# KUBODriver_MCU.net
KiCad netlist of a schematic drawn in Altium Designer
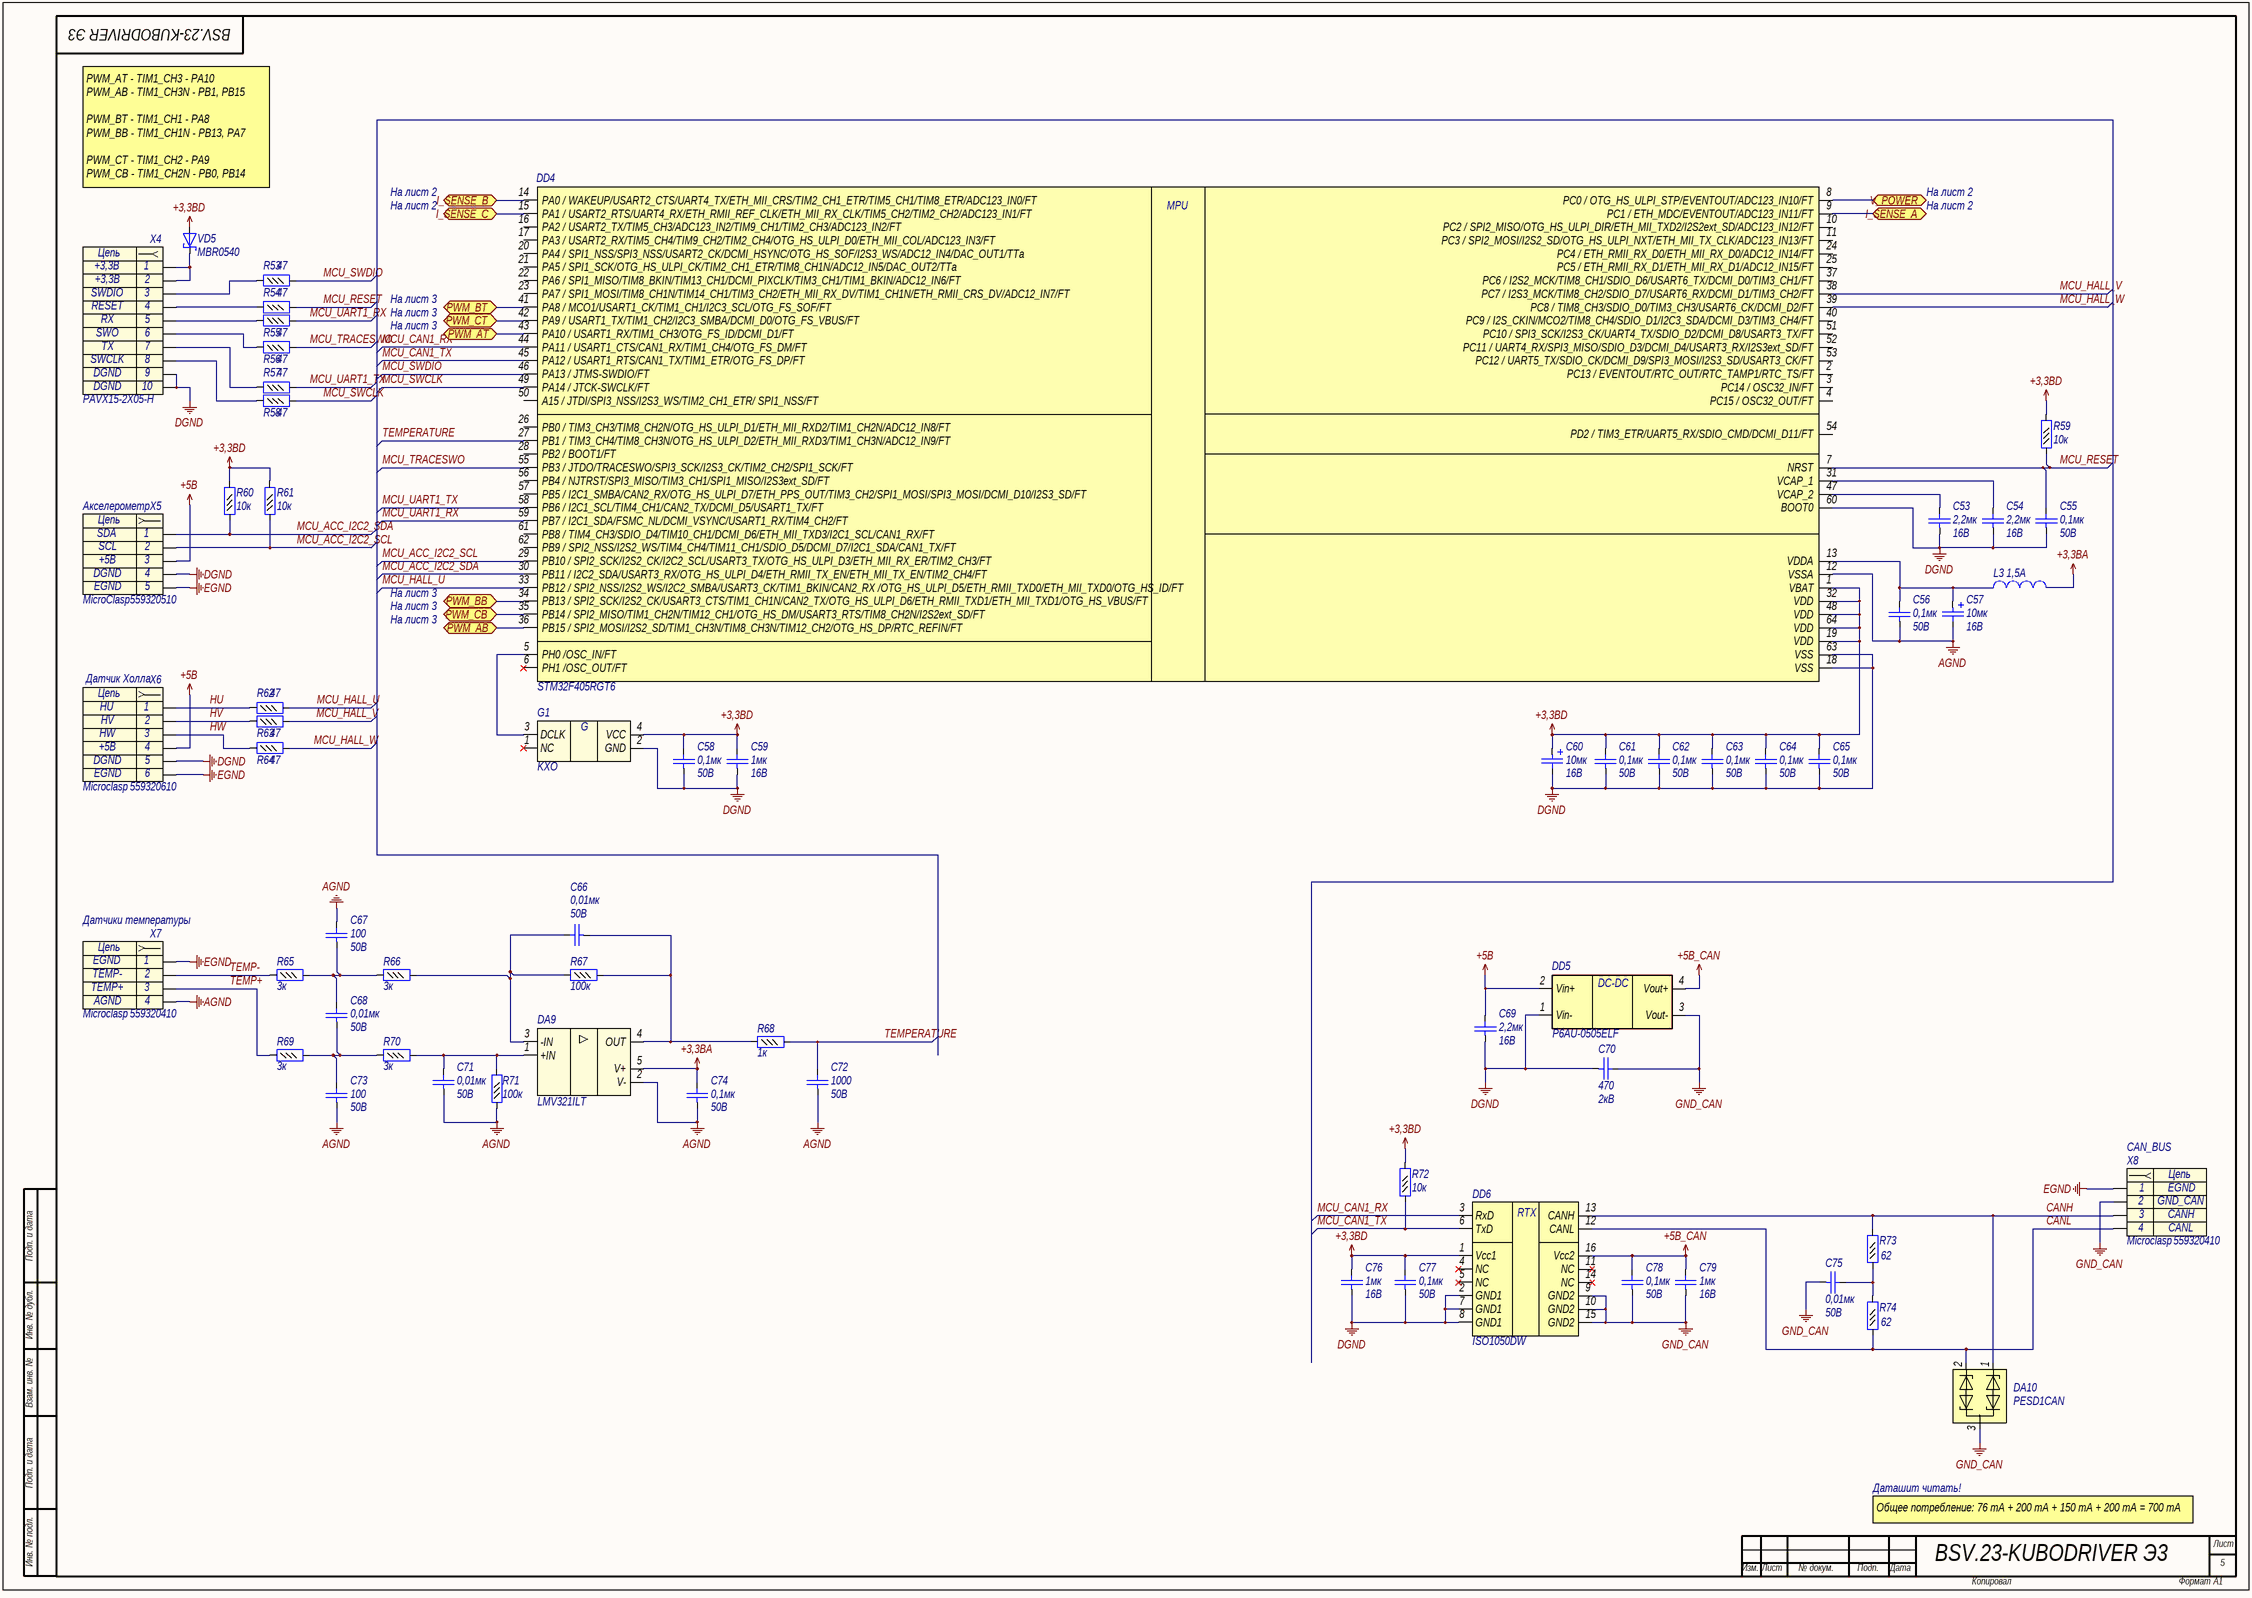
[diagram p0: KUBODriver_MCU.SchDoc]

(export (version "E")
  (design (tool "Eeschema 10.0.6"))
  (components
    (comp (ref "C53")
      (value "2,2мк")
      (footprint "C0603")
      (description "Конденсатор")
      (fields (field (name "VOLTAGE") "16B") (field (name "PART NUMBER") "GRM188Z71C225ME43J"))
      (libsource (lib "MOP44") (part "Capacitor"))
    )
    (comp (ref "C54")
      (value "2,2мк")
      (footprint "C0603")
      (description "Конденсатор")
      (fields (field (name "VOLTAGE") "16B") (field (name "PART NUMBER") "GRM188Z71C225ME43J"))
      (libsource (lib "MOP44") (part "Capacitor"))
    )
    (comp (ref "C55")
      (value "0,1мк")
      (footprint "C0402")
      (description "Конденсатор")
      (fields
        (field (name "VOLTAGE") "50В")
        (field (name "PART NUMBER") "GRM155R71H104KE14D ")
        (field (name "Comment") "Capacitor")
      )
      (libsource (lib "MOP44") (part "Capacitor"))
    )
    (comp (ref "C56")
      (value "0,1мк")
      (footprint "C0402")
      (description "Конденсатор")
      (fields
        (field (name "VOLTAGE") "50В")
        (field (name "PART NUMBER") "GRM155R71H104KE14D ")
        (field (name "Comment") "Capacitor")
      )
      (libsource (lib "MOP44") (part "Capacitor"))
    )
    (comp (ref "C57")
      (value "10мк")
      (footprint "TANTAL CASE A")
      (description "Конденсатор полярный")
      (fields
        (field (name "VOLTAGE") "16В")
        (field (name "PART NUMBER") "293D106X9016A2TE3")
        (field (name "Comment") "Capacitor_pol")
      )
      (libsource (lib "MOP44") (part "Capacitor_pol"))
    )
    (comp (ref "C58")
      (value "0,1мк")
      (footprint "C0402")
      (description "Конденсатор")
      (fields
        (field (name "VOLTAGE") "50В")
        (field (name "PART NUMBER") "GRM155R71H104KE14D ")
        (field (name "Comment") "Capacitor")
      )
      (libsource (lib "MOP44") (part "Capacitor"))
    )
    (comp (ref "C59")
      (value "1мк")
      (footprint "C0603")
      (description "Конденсатор")
      (fields
        (field (name "VOLTAGE") "16B")
        (field (name "PART NUMBER") "GRM188R71C105KA12D**")
        (field (name "Comment") "Capacitor")
      )
      (libsource (lib "MOP44") (part "Capacitor"))
    )
    (comp (ref "C60")
      (value "10мк")
      (footprint "TANTAL CASE A")
      (description "Конденсатор полярный")
      (fields
        (field (name "VOLTAGE") "16В")
        (field (name "PART NUMBER") "293D106X9016A2TE3")
        (field (name "Comment") "Capacitor_pol")
      )
      (libsource (lib "MOP44") (part "Capacitor_pol"))
    )
    (comp (ref "C61")
      (value "0,1мк")
      (footprint "C0402")
      (description "Конденсатор")
      (fields
        (field (name "VOLTAGE") "50В")
        (field (name "PART NUMBER") "GRM155R71H104KE14D ")
        (field (name "Comment") "Capacitor")
      )
      (libsource (lib "MOP44") (part "Capacitor"))
    )
    (comp (ref "C62")
      (value "0,1мк")
      (footprint "C0402")
      (description "Конденсатор")
      (fields
        (field (name "VOLTAGE") "50В")
        (field (name "PART NUMBER") "GRM155R71H104KE14D ")
        (field (name "Comment") "Capacitor")
      )
      (libsource (lib "MOP44") (part "Capacitor"))
    )
    (comp (ref "C63")
      (value "0,1мк")
      (footprint "C0402")
      (description "Конденсатор")
      (fields
        (field (name "VOLTAGE") "50В")
        (field (name "PART NUMBER") "GRM155R71H104KE14D ")
        (field (name "Comment") "Capacitor")
      )
      (libsource (lib "MOP44") (part "Capacitor"))
    )
    (comp (ref "C64")
      (value "0,1мк")
      (footprint "C0402")
      (description "Конденсатор")
      (fields
        (field (name "VOLTAGE") "50В")
        (field (name "PART NUMBER") "GRM155R71H104KE14D ")
        (field (name "Comment") "Capacitor")
      )
      (libsource (lib "MOP44") (part "Capacitor"))
    )
    (comp (ref "C65")
      (value "0,1мк")
      (footprint "C0402")
      (description "Конденсатор")
      (fields
        (field (name "VOLTAGE") "50В")
        (field (name "PART NUMBER") "GRM155R71H104KE14D ")
        (field (name "Comment") "Capacitor")
      )
      (libsource (lib "MOP44") (part "Capacitor"))
    )
    (comp (ref "C66")
      (value "0,01мк")
      (footprint "C0402")
      (description "Конденсатор")
      (fields
        (field (name "VOLTAGE") "50B")
        (field (name "PART NUMBER") "GRM155R71H103K")
        (field (name "Comment") "Capacitor")
      )
      (libsource (lib "MOP44") (part "Capacitor"))
    )
    (comp (ref "C67")
      (value "100")
      (footprint "C0402")
      (description "Конденсатор")
      (fields
        (field (name "VOLTAGE") "50B")
        (field (name "PART NUMBER") "GRM1535C1H101J")
        (field (name "Comment") "Capacitor")
      )
      (libsource (lib "MOP44") (part "Capacitor"))
    )
    (comp (ref "C68")
      (value "0,01мк")
      (footprint "C0402")
      (description "Конденсатор")
      (fields
        (field (name "VOLTAGE") "50B")
        (field (name "PART NUMBER") "GRM155R71H103K")
        (field (name "Comment") "Capacitor")
      )
      (libsource (lib "MOP44") (part "Capacitor"))
    )
    (comp (ref "C69")
      (value "2,2мк")
      (footprint "C0603")
      (description "Конденсатор")
      (fields (field (name "VOLTAGE") "16B") (field (name "PART NUMBER") "GRM188Z71C225ME43J"))
      (libsource (lib "MOP44") (part "Capacitor"))
    )
    (comp (ref "C70")
      (value "470")
      (footprint "C1206")
      (description "Конденсатор")
      (fields
        (field (name "VOLTAGE") "2кВ")
        (field (name "PART NUMBER") "CC1206KKX7RDBB471 ")
        (field (name "Comment") "Capacitor")
      )
      (libsource (lib "MOP44") (part "Capacitor"))
    )
    (comp (ref "C71")
      (value "0,01мк")
      (footprint "C0402")
      (description "Конденсатор")
      (fields
        (field (name "VOLTAGE") "50B")
        (field (name "PART NUMBER") "GRM155R71H103K")
        (field (name "Comment") "Capacitor")
      )
      (libsource (lib "MOP44") (part "Capacitor"))
    )
    (comp (ref "C72")
      (value "1000")
      (footprint "C0402")
      (description "Конденсатор")
      (fields
        (field (name "VOLTAGE") "50B")
        (field (name "PART NUMBER") "GRM1555C1H102J")
        (field (name "Comment") "Capacitor")
      )
      (libsource (lib "MOP44") (part "Capacitor"))
    )
    (comp (ref "C73")
      (value "100")
      (footprint "C0402")
      (description "Конденсатор")
      (fields
        (field (name "VOLTAGE") "50B")
        (field (name "PART NUMBER") "GRM1535C1H101J")
        (field (name "Comment") "Capacitor")
      )
      (libsource (lib "MOP44") (part "Capacitor"))
    )
    (comp (ref "C74")
      (value "0,1мк")
      (footprint "C0402")
      (description "Конденсатор")
      (fields
        (field (name "VOLTAGE") "50В")
        (field (name "PART NUMBER") "GRM155R71H104KE14D ")
        (field (name "Comment") "Capacitor")
      )
      (libsource (lib "MOP44") (part "Capacitor"))
    )
    (comp (ref "C75")
      (value "0,01мк")
      (footprint "C0402")
      (description "Конденсатор")
      (fields
        (field (name "VOLTAGE") "50B")
        (field (name "PART NUMBER") "GRM155R71H103K")
        (field (name "Comment") "Capacitor")
      )
      (libsource (lib "MOP44") (part "Capacitor"))
    )
    (comp (ref "C76")
      (value "1мк")
      (footprint "C0603")
      (description "Конденсатор")
      (fields
        (field (name "VOLTAGE") "16B")
        (field (name "PART NUMBER") "GRM188R71C105KA12D**")
        (field (name "Comment") "Capacitor")
      )
      (libsource (lib "MOP44") (part "Capacitor"))
    )
    (comp (ref "C77")
      (value "0,1мк")
      (footprint "C0402")
      (description "Конденсатор")
      (fields
        (field (name "VOLTAGE") "50В")
        (field (name "PART NUMBER") "GRM155R71H104KE14D ")
        (field (name "Comment") "Capacitor")
      )
      (libsource (lib "MOP44") (part "Capacitor"))
    )
    (comp (ref "C78")
      (value "0,1мк")
      (footprint "C0402")
      (description "Конденсатор")
      (fields
        (field (name "VOLTAGE") "50В")
        (field (name "PART NUMBER") "GRM155R71H104KE14D ")
        (field (name "Comment") "Capacitor")
      )
      (libsource (lib "MOP44") (part "Capacitor"))
    )
    (comp (ref "C79")
      (value "1мк")
      (footprint "C0603")
      (description "Конденсатор")
      (fields
        (field (name "VOLTAGE") "16B")
        (field (name "PART NUMBER") "GRM188R71C105KA12D**")
        (field (name "Comment") "Capacitor")
      )
      (libsource (lib "MOP44") (part "Capacitor"))
    )
    (comp (ref "DA9")
      (value "LMV321ILT")
      (footprint "SOT23-5")
      (description "HIGH-DRIVE OPERATIONAL AMPLIFIERS WITH SHUTDOWN")
      (libsource (lib "MOP44") (part "LMV321ILT"))
    )
    (comp (ref "DA10")
      (value "PESD")
      (footprint "SOT23-3")
      (description "TVS")
      (fields (field (name "PART NUMBER") "PESD1CAN"))
      (libsource (lib "MOP44") (part "PESD"))
    )
    (comp (ref "DD4")
      (value "STM32F405RGT6")
      (footprint "LQFP64")
      (libsource (lib "MOP44") (part "STM32F405RGT6"))
    )
    (comp (ref "DD5")
      (value "P6AU-xxxxELF")
      (footprint "SIP4")
      (description "DC/DC преобразователь")
      (fields (field (name "PART NUMBER") "P6AU-0505ELF") (field (name "MANUFACTURER") "PEAK Electronics"))
      (libsource (lib "MOP44") (part "P6AU-xxxxELF"))
    )
    (comp (ref "DD6")
      (value "~")
      (footprint "SO16")
      (description "Isolated CAN Transceiver")
      (fields (field (name "PART NUMBER") "ISO1050DW"))
      (libsource (lib "MOP44") (part "ISO1050DW"))
    )
    (comp (ref "G1")
      (value "KXO")
      (footprint "QSMD7x5.2x1.8")
      (description "Кварц. генер. 32.768 МГц (HCMOS/TTL)")
      (fields (field (name "PART NUMBER") "KXO-V97"))
      (libsource (lib "MOP44") (part "KXO"))
    )
    (comp (ref "L3")
      (value "Inductor")
      (footprint "L0603")
      (description "EMI Suppression Filter")
      (fields (field (name "RATED CURRENT") "1,5A") (field (name "PART NUMBER") "BLM18PG181SN1D"))
      (libsource (lib "MOP44") (part "Inductor"))
    )
    (comp (ref "R53")
      (value "47")
      (footprint "R0402")
      (description "Резистор")
      (fields (field (name "PART NUMBER") "RC0402FR-0747RL") (field (name "POWER") "0,062Вт"))
      (libsource (lib "MOP44") (part "Resistor_0,062Вт"))
    )
    (comp (ref "R54")
      (value "47")
      (footprint "R0402")
      (description "Резистор")
      (fields (field (name "PART NUMBER") "RC0402FR-0747RL") (field (name "POWER") "0,062Вт"))
      (libsource (lib "MOP44") (part "Resistor_0,062Вт"))
    )
    (comp (ref "R55")
      (value "47")
      (footprint "R0402")
      (description "Резистор")
      (fields (field (name "PART NUMBER") "RC0402FR-0747RL") (field (name "POWER") "0,062Вт"))
      (libsource (lib "MOP44") (part "Resistor_0,062Вт"))
    )
    (comp (ref "R56")
      (value "47")
      (footprint "R0402")
      (description "Резистор")
      (fields (field (name "PART NUMBER") "RC0402FR-0747RL") (field (name "POWER") "0,062Вт"))
      (libsource (lib "MOP44") (part "Resistor_0,062Вт"))
    )
    (comp (ref "R57")
      (value "47")
      (footprint "R0402")
      (description "Резистор")
      (fields (field (name "PART NUMBER") "RC0402FR-0747RL") (field (name "POWER") "0,062Вт"))
      (libsource (lib "MOP44") (part "Resistor_0,062Вт"))
    )
    (comp (ref "R58")
      (value "47")
      (footprint "R0402")
      (description "Резистор")
      (fields (field (name "PART NUMBER") "RC0402FR-0747RL") (field (name "POWER") "0,062Вт"))
      (libsource (lib "MOP44") (part "Resistor_0,062Вт"))
    )
    (comp (ref "R59")
      (value "10к")
      (footprint "R0402")
      (description "Резистор")
      (fields (field (name "PART NUMBER") "RC0402FR-0710KL") (field (name "POWER") "0,062Вт"))
      (libsource (lib "") (part "Resistor_0,062Вт_1"))
    )
    (comp (ref "R60")
      (value "10к")
      (footprint "R0402")
      (description "Резистор")
      (fields (field (name "PART NUMBER") "RC0402FR-0710KL") (field (name "POWER") "0,062Вт"))
      (libsource (lib "") (part "Resistor_0,062Вт_1"))
    )
    (comp (ref "R61")
      (value "10к")
      (footprint "R0402")
      (description "Резистор")
      (fields (field (name "PART NUMBER") "RC0402FR-0710KL") (field (name "POWER") "0,062Вт"))
      (libsource (lib "") (part "Resistor_0,062Вт_1"))
    )
    (comp (ref "R62")
      (value "47")
      (footprint "R0402")
      (description "Резистор")
      (fields (field (name "PART NUMBER") "RC0402FR-0747RL") (field (name "POWER") "0,062Вт"))
      (libsource (lib "MOP44") (part "Resistor_0,062Вт"))
    )
    (comp (ref "R63")
      (value "47")
      (footprint "R0402")
      (description "Резистор")
      (fields (field (name "PART NUMBER") "RC0402FR-0747RL") (field (name "POWER") "0,062Вт"))
      (libsource (lib "MOP44") (part "Resistor_0,062Вт"))
    )
    (comp (ref "R64")
      (value "47")
      (footprint "R0402")
      (description "Резистор")
      (fields (field (name "PART NUMBER") "RC0402FR-0747RL") (field (name "POWER") "0,062Вт"))
      (libsource (lib "MOP44") (part "Resistor_0,062Вт"))
    )
    (comp (ref "R65")
      (value "3к")
      (footprint "R0402")
      (description "Резистор")
      (fields (field (name "PART NUMBER") "RC0402FR-073KL") (field (name "POWER") "0,062Вт"))
      (libsource (lib "MOP44") (part "Resistor_0,062Вт"))
    )
    (comp (ref "R66")
      (value "3к")
      (footprint "R0402")
      (description "Резистор")
      (fields (field (name "PART NUMBER") "RC0402FR-073KL") (field (name "POWER") "0,062Вт"))
      (libsource (lib "MOP44") (part "Resistor_0,062Вт"))
    )
    (comp (ref "R67")
      (value "100к")
      (footprint "R0402")
      (description "Резистор")
      (fields (field (name "PART NUMBER") "RC0402FR-07100KL") (field (name "POWER") "0,062Вт"))
      (libsource (lib "MOP44") (part "Resistor_0,062Вт"))
    )
    (comp (ref "R68")
      (value "1к")
      (footprint "R0402")
      (description "Резистор")
      (fields (field (name "PART NUMBER") "RC0402FR-071KL") (field (name "POWER") "0,062Вт"))
      (libsource (lib "MOP44") (part "Resistor_0,062Вт"))
    )
    (comp (ref "R69")
      (value "3к")
      (footprint "R0402")
      (description "Резистор")
      (fields (field (name "PART NUMBER") "RC0402FR-073KL") (field (name "POWER") "0,062Вт"))
      (libsource (lib "MOP44") (part "Resistor_0,062Вт"))
    )
    (comp (ref "R70")
      (value "3к")
      (footprint "R0402")
      (description "Резистор")
      (fields (field (name "PART NUMBER") "RC0402FR-073KL") (field (name "POWER") "0,062Вт"))
      (libsource (lib "MOP44") (part "Resistor_0,062Вт"))
    )
    (comp (ref "R71")
      (value "100к")
      (footprint "R0402")
      (description "Резистор")
      (fields (field (name "PART NUMBER") "RC0402FR-07100KL") (field (name "POWER") "0,062Вт"))
      (libsource (lib "") (part "Resistor_0,062Вт_1"))
    )
    (comp (ref "R72")
      (value "10к")
      (footprint "R0402")
      (description "Резистор")
      (fields (field (name "PART NUMBER") "RC0402FR-0710KL") (field (name "POWER") "0,062Вт"))
      (libsource (lib "") (part "Resistor_0,062Вт_1"))
    )
    (comp (ref "R73")
      (value "62")
      (footprint "R0402")
      (description "Резистор")
      (fields (field (name "PART NUMBER") "RC0402FR-0762RL") (field (name "POWER") "0,062Вт"))
      (libsource (lib "") (part "Resistor_0,062Вт_1"))
    )
    (comp (ref "R74")
      (value "62")
      (footprint "R0402")
      (description "Резистор")
      (fields (field (name "PART NUMBER") "RC0402FR-0762RL") (field (name "POWER") "0,062Вт"))
      (libsource (lib "") (part "Resistor_0,062Вт_1"))
    )
    (comp (ref "VD5")
      (value "DiodeSchottky")
      (footprint "SOD-123")
      (description "Диод Шоттки")
      (fields (field (name "PART NUMBER") "MBR0540"))
      (libsource (lib "MOP44") (part "DiodeSchottky"))
    )
    (comp (ref "X4")
      (value "Header_10_sct")
      (footprint "PAVX15-2X05-H")
      (description "Разъем - 10 конт. розетка")
      (fields (field (name "PART NUMBER") "PAVX15-2X05-H"))
      (libsource (lib "MOP44") (part "Header_10_sct"))
    )
    (comp (ref "X5")
      (value "Акселерометр")
      (footprint "MOLEX_559320510")
      (description "Разъем - 5 конт. розетка")
      (fields (field (name "PART NAME") "MicroClasp") (field (name "PART NUMBER") "559320510"))
      (libsource (lib "MOP44") (part "Header_5_sct"))
    )
    (comp (ref "X6")
      (value "Датчик Холла")
      (footprint "MOLEX_559320610")
      (description "Разъем - 6 конт. розетка")
      (fields (field (name "PART NUMBER") "559320610"))
      (libsource (lib "MOP44") (part "Header_6_sct"))
    )
    (comp (ref "X7")
      (value "Датчики температуры")
      (footprint "MOLEX_559320410")
      (description "Разъем - 4 конт. розетка")
      (fields (field (name "PART NUMBER") "559320410"))
      (libsource (lib "") (part "Header_4_sct_1"))
    )
    (comp (ref "X8")
      (value "CAN_BUS")
      (footprint "MOLEX_559320410")
      (description "Разъем - 4 конт. розетка")
      (fields (field (name "PART NUMBER") "559320410"))
      (libsource (lib "MOP44") (part "Header_4_sct"))
    )
  )
  (nets
    (net (code "1") (name "+3,3BA") (class "Default")
      (node (ref "C74") (pin "2") (pinfunction "2_2") (pintype "passive"))
      (node (ref "DA9") (pin "5") (pinfunction "V+_5") (pintype "passive"))
      (node (ref "L3") (pin "2") (pinfunction "2_2") (pintype "passive"))
    )
    (net (code "2") (name "+3,3BD") (class "Default")
      (node (ref "C58") (pin "2") (pinfunction "2_2") (pintype "passive"))
      (node (ref "C59") (pin "2") (pinfunction "2_2") (pintype "passive"))
      (node (ref "C60") (pin "1") (pinfunction "1_1") (pintype "passive"))
      (node (ref "C61") (pin "2") (pinfunction "2_2") (pintype "passive"))
      (node (ref "C62") (pin "2") (pinfunction "2_2") (pintype "passive"))
      (node (ref "C63") (pin "2") (pinfunction "2_2") (pintype "passive"))
      (node (ref "C64") (pin "2") (pinfunction "2_2") (pintype "passive"))
      (node (ref "C65") (pin "2") (pinfunction "2_2") (pintype "passive"))
      (node (ref "C76") (pin "2") (pinfunction "2_2") (pintype "passive"))
      (node (ref "C77") (pin "2") (pinfunction "2_2") (pintype "passive"))
      (node (ref "DD4") (pin "1") (pinfunction "VBAT_1") (pintype "passive"))
      (node (ref "DD4") (pin "19") (pinfunction "VDD_19") (pintype "passive"))
      (node (ref "DD4") (pin "32") (pinfunction "VDD_32") (pintype "passive"))
      (node (ref "DD4") (pin "48") (pinfunction "VDD_48") (pintype "passive"))
      (node (ref "DD4") (pin "64") (pinfunction "VDD_64") (pintype "passive"))
      (node (ref "DD6") (pin "1") (pinfunction "Vcc1_1") (pintype "passive"))
      (node (ref "G1") (pin "4") (pinfunction "VCC_4") (pintype "power_in"))
      (node (ref "R59") (pin "2") (pinfunction "2_2") (pintype "passive"))
      (node (ref "R60") (pin "2") (pinfunction "2_2") (pintype "passive"))
      (node (ref "R61") (pin "2") (pinfunction "2_2") (pintype "passive"))
      (node (ref "R72") (pin "2") (pinfunction "2_2") (pintype "passive"))
      (node (ref "VD5") (pin "2") (pinfunction "A_2") (pintype "passive"))
    )
    (net (code "3") (name "+5B") (class "Default")
      (node (ref "C69") (pin "2") (pinfunction "2_2") (pintype "passive"))
      (node (ref "DD5") (pin "2") (pinfunction "Vin+_2") (pintype "passive"))
      (node (ref "X5") (pin "3") (pinfunction "3_3") (pintype "passive"))
      (node (ref "X6") (pin "4") (pinfunction "4_4") (pintype "passive"))
    )
    (net (code "4") (name "+5B_CAN") (class "Default")
      (node (ref "C78") (pin "2") (pinfunction "2_2") (pintype "passive"))
      (node (ref "C79") (pin "2") (pinfunction "2_2") (pintype "passive"))
      (node (ref "DD5") (pin "4") (pinfunction "Vout+_4") (pintype "passive"))
      (node (ref "DD6") (pin "16") (pinfunction "Vcc2_16") (pintype "passive"))
    )
    (net (code "5") (name "/CANH") (class "Default")
      (node (ref "DA10") (pin "1") (pintype "passive"))
      (node (ref "DD6") (pin "13") (pinfunction "CANH_13") (pintype "passive"))
      (node (ref "R73") (pin "2") (pinfunction "2_2") (pintype "passive"))
      (node (ref "X8") (pin "3") (pinfunction "3_3") (pintype "passive"))
    )
    (net (code "6") (name "/CANL") (class "Default")
      (node (ref "DA10") (pin "2") (pinfunction "1_2") (pintype "passive"))
      (node (ref "DD6") (pin "12") (pinfunction "CANL_12") (pintype "passive"))
      (node (ref "R74") (pin "1") (pinfunction "1_1") (pintype "passive"))
      (node (ref "X8") (pin "4") (pinfunction "4_4") (pintype "passive"))
    )
    (net (code "7") (name "/HU") (class "Default")
      (node (ref "R62") (pin "1") (pinfunction "1_1") (pintype "passive"))
      (node (ref "X6") (pin "1") (pinfunction "1_1") (pintype "passive"))
    )
    (net (code "8") (name "/HV") (class "Default")
      (node (ref "R63") (pin "1") (pinfunction "1_1") (pintype "passive"))
      (node (ref "X6") (pin "2") (pinfunction "2_2") (pintype "passive"))
    )
    (net (code "9") (name "/HW") (class "Default")
      (node (ref "R64") (pin "1") (pinfunction "1_1") (pintype "passive"))
      (node (ref "X6") (pin "3") (pinfunction "3_3") (pintype "passive"))
    )
    (net (code "10") (name "/I_SENSE_A") (class "Default")
      (node (ref "DD4") (pin "9") (pinfunction "PC1_/_ETH_MDC/EVENTOUT/ADC123_IN11/FT_9") (pintype "passive"))
    )
    (net (code "11") (name "/I_SENSE_B") (class "Default")
      (node (ref "DD4") (pin "14") (pinfunction "PA0_/_WAKEUP/USART2_CTS/UART4_TX/ETH_MII_CRS/TIM2_CH1_ETR/TIM5_CH1/TIM8_ETR/ADC123_IN0/FT_14") (pintype "passive"))
    )
    (net (code "12") (name "/I_SENSE_C") (class "Default")
      (node (ref "DD4") (pin "15") (pinfunction "PA1_/_USART2_RTS/UART4_RX/ETH_RMII_REF_CLK/ETH_MII_RX_CLK/TIM5_CH2/TIM2_CH2/ADC123_IN1/FT_15") (pintype "passive"))
    )
    (net (code "13") (name "/MCU_ACC_I2C2_SCL") (class "Default")
      (node (ref "DD4") (pin "29") (pinfunction "PB10_/_SPI2_SCK/I2S2_CK/I2C2_SCL/USART3_TX/OTG_HS_ULPI_D3/ETH_MII_RX_ER/TIM2_CH3/FT_29") (pintype "passive"))
      (node (ref "R61") (pin "1") (pinfunction "1_1") (pintype "passive"))
      (node (ref "X5") (pin "2") (pinfunction "2_2") (pintype "passive"))
    )
    (net (code "14") (name "/MCU_ACC_I2C2_SDA") (class "Default")
      (node (ref "DD4") (pin "30") (pinfunction "PB11_/_I2C2_SDA/USART3_RX/OTG_HS_ULPI_D4/ETH_RMII_TX_EN/ETH_MII_TX_EN/TIM2_CH4/FT_30") (pintype "passive"))
      (node (ref "R60") (pin "1") (pinfunction "1_1") (pintype "passive"))
      (node (ref "X5") (pin "1") (pinfunction "1_1") (pintype "passive"))
    )
    (net (code "15") (name "/MCU_CAN1_RX") (class "Default")
      (node (ref "DD4") (pin "44") (pinfunction "PA11_/_USART1_CTS/CAN1_RX/TIM1_CH4/OTG_FS_DM/FT_44") (pintype "passive"))
      (node (ref "DD6") (pin "3") (pinfunction "RxD_3") (pintype "passive"))
    )
    (net (code "16") (name "/MCU_CAN1_TX") (class "Default")
      (node (ref "DD4") (pin "45") (pinfunction "PA12_/_USART1_RTS/CAN1_TX/TIM1_ETR/OTG_FS_DP/FT_45") (pintype "passive"))
      (node (ref "DD6") (pin "6") (pinfunction "TxD_6") (pintype "passive"))
      (node (ref "R72") (pin "1") (pinfunction "1_1") (pintype "passive"))
    )
    (net (code "17") (name "/MCU_HALL_U") (class "Default")
      (node (ref "DD4") (pin "33") (pinfunction "PB12_/_SPI2_NSS/I2S2_WS/I2C2_SMBA/USART3_CK/TIM1_BKIN/CAN2_RX_/OTG_HS_ULPI_D5/ETH_RMII_TXD0/ETH_MII_TXD0/OTG_HS_ID/FT_33") (pintype "passive"))
      (node (ref "R62") (pin "2") (pinfunction "2_2") (pintype "passive"))
    )
    (net (code "18") (name "/MCU_HALL_V") (class "Default")
      (node (ref "DD4") (pin "38") (pinfunction "PC7_/_I2S3_MCK/TIM8_CH2/SDIO_D7/USART6_RX/DCMI_D1/TIM3_CH2/FT_38") (pintype "passive"))
      (node (ref "R63") (pin "2") (pinfunction "2_2") (pintype "passive"))
    )
    (net (code "19") (name "/MCU_HALL_W") (class "Default")
      (node (ref "DD4") (pin "39") (pinfunction "PC8_/_TIM8_CH3/SDIO_D0/TIM3_CH3/USART6_CK/DCMI_D2/FT_39") (pintype "passive"))
      (node (ref "R64") (pin "2") (pinfunction "2_2") (pintype "passive"))
    )
    (net (code "20") (name "/MCU_RESET") (class "Default")
      (node (ref "C55") (pin "2") (pinfunction "2_2") (pintype "passive"))
      (node (ref "DD4") (pin "7") (pinfunction "NRST_7") (pintype "passive"))
      (node (ref "R54") (pin "2") (pinfunction "2_2") (pintype "passive"))
      (node (ref "R59") (pin "1") (pinfunction "1_1") (pintype "passive"))
    )
    (net (code "21") (name "/MCU_SWCLK") (class "Default")
      (node (ref "DD4") (pin "49") (pinfunction "PA14_/_JTCK-SWCLK/FT_49") (pintype "passive"))
      (node (ref "R58") (pin "2") (pinfunction "2_2") (pintype "passive"))
    )
    (net (code "22") (name "/MCU_SWDIO") (class "Default")
      (node (ref "DD4") (pin "46") (pinfunction "PA13_/_JTMS-SWDIO/FT_46") (pintype "passive"))
      (node (ref "R53") (pin "2") (pinfunction "2_2") (pintype "passive"))
    )
    (net (code "23") (name "/MCU_TRACESWO") (class "Default")
      (node (ref "DD4") (pin "55") (pinfunction "PB3_/_JTDO/TRACESWO/SPI3_SCK/I2S3_CK/TIM2_CH2/SPI1_SCK/FT_55") (pintype "passive"))
      (node (ref "R56") (pin "2") (pinfunction "2_2") (pintype "passive"))
    )
    (net (code "24") (name "/MCU_UART1_RX") (class "Default")
      (node (ref "DD4") (pin "59") (pinfunction "PB7_/_I2C1_SDA/FSMC_NL/DCMI_VSYNC/USART1_RX/TIM4_CH2/FT_59") (pintype "passive"))
      (node (ref "R55") (pin "2") (pinfunction "2_2") (pintype "passive"))
    )
    (net (code "25") (name "/MCU_UART1_TX") (class "Default")
      (node (ref "DD4") (pin "58") (pinfunction "PB6_/_I2C1_SCL/TIM4_CH1/CAN2_TX/DCMI_D5/USART1_TX/FT_58") (pintype "passive"))
      (node (ref "R57") (pin "2") (pinfunction "2_2") (pintype "passive"))
    )
    (net (code "26") (name "/PWM_AB") (class "Default")
      (node (ref "DD4") (pin "36") (pinfunction "PB15_/_SPI2_MOSI/I2S2_SD/TIM1_CH3N/TIM8_CH3N/TIM12_CH2/OTG_HS_DP/RTC_REFIN/FT_36") (pintype "passive"))
    )
    (net (code "27") (name "/PWM_AT") (class "Default")
      (node (ref "DD4") (pin "43") (pinfunction "PA10_/_USART1_RX/TIM1_CH3/OTG_FS_ID/DCMI_D1/FT_43") (pintype "passive"))
    )
    (net (code "28") (name "/PWM_BB") (class "Default")
      (node (ref "DD4") (pin "34") (pinfunction "PB13_/_SPI2_SCK/I2S2_CK/USART3_CTS/TIM1_CH1N/CAN2_TX/OTG_HS_ULPI_D6/ETH_RMII_TXD1/ETH_MII_TXD1/OTG_HS_VBUS/FT_34") (pintype "passive"))
    )
    (net (code "29") (name "/PWM_BT") (class "Default")
      (node (ref "DD4") (pin "41") (pinfunction "PA8_/_MCO1/USART1_CK/TIM1_CH1/I2C3_SCL/OTG_FS_SOF/FT_41") (pintype "passive"))
    )
    (net (code "30") (name "/PWM_CB") (class "Default")
      (node (ref "DD4") (pin "35") (pinfunction "PB14_/_SPI2_MISO/TIM1_CH2N/TIM12_CH1/OTG_HS_DM/USART3_RTS/TIM8_CH2N/I2S2ext_SD/FT_35") (pintype "passive"))
    )
    (net (code "31") (name "/PWM_CT") (class "Default")
      (node (ref "DD4") (pin "42") (pinfunction "PA9_/_USART1_TX/TIM1_CH2/I2C3_SMBA/DCMI_D0/OTG_FS_VBUS/FT_42") (pintype "passive"))
    )
    (net (code "32") (name "/TEMP+") (class "Default")
      (node (ref "R69") (pin "1") (pinfunction "1_1") (pintype "passive"))
      (node (ref "X7") (pin "3") (pinfunction "3_3") (pintype "passive"))
    )
    (net (code "33") (name "/TEMP-") (class "Default")
      (node (ref "R65") (pin "1") (pinfunction "1_1") (pintype "passive"))
      (node (ref "X7") (pin "2") (pinfunction "2_2") (pintype "passive"))
    )
    (net (code "34") (name "/TEMPERATURE") (class "Default")
      (node (ref "C72") (pin "2") (pinfunction "2_2") (pintype "passive"))
      (node (ref "DD4") (pin "27") (pinfunction "PB1_/_TIM3_CH4/TIM8_CH3N/OTG_HS_ULPI_D2/ETH_MII_RXD3/TIM1_CH3N/ADC12_IN9/FT_27") (pintype "passive"))
      (node (ref "R68") (pin "2") (pinfunction "2_2") (pintype "passive"))
    )
    (net (code "35") (name "/V_POWER") (class "Default")
      (node (ref "DD4") (pin "8") (pinfunction "PC0_/_OTG_HS_ULPI_STP/EVENTOUT/ADC123_IN10/FT_8") (pintype "passive"))
    )
    (net (code "36") (name "AGND") (class "Default")
      (node (ref "C56") (pin "1") (pinfunction "1_1") (pintype "passive"))
      (node (ref "C57") (pin "2") (pinfunction "2_2") (pintype "passive"))
      (node (ref "C67") (pin "2") (pinfunction "2_2") (pintype "passive"))
      (node (ref "C71") (pin "1") (pinfunction "1_1") (pintype "passive"))
      (node (ref "C72") (pin "1") (pinfunction "1_1") (pintype "passive"))
      (node (ref "C73") (pin "1") (pinfunction "1_1") (pintype "passive"))
      (node (ref "C74") (pin "1") (pinfunction "1_1") (pintype "passive"))
      (node (ref "DA9") (pin "2") (pinfunction "V-_2") (pintype "passive"))
      (node (ref "DD4") (pin "12") (pinfunction "VSSA_12") (pintype "passive"))
      (node (ref "R71") (pin "1") (pinfunction "1_1") (pintype "passive"))
      (node (ref "X7") (pin "4") (pinfunction "4_4") (pintype "passive"))
    )
    (net (code "37") (name "DGND") (class "Default")
      (node (ref "C53") (pin "1") (pinfunction "1_1") (pintype "passive"))
      (node (ref "C54") (pin "1") (pinfunction "1_1") (pintype "passive"))
      (node (ref "C55") (pin "1") (pinfunction "1_1") (pintype "passive"))
      (node (ref "C58") (pin "1") (pinfunction "1_1") (pintype "passive"))
      (node (ref "C59") (pin "1") (pinfunction "1_1") (pintype "passive"))
      (node (ref "C60") (pin "2") (pinfunction "2_2") (pintype "passive"))
      (node (ref "C61") (pin "1") (pinfunction "1_1") (pintype "passive"))
      (node (ref "C62") (pin "1") (pinfunction "1_1") (pintype "passive"))
      (node (ref "C63") (pin "1") (pinfunction "1_1") (pintype "passive"))
      (node (ref "C64") (pin "1") (pinfunction "1_1") (pintype "passive"))
      (node (ref "C65") (pin "1") (pinfunction "1_1") (pintype "passive"))
      (node (ref "C69") (pin "1") (pinfunction "1_1") (pintype "passive"))
      (node (ref "C70") (pin "1") (pinfunction "1_1") (pintype "passive"))
      (node (ref "C76") (pin "1") (pinfunction "1_1") (pintype "passive"))
      (node (ref "C77") (pin "1") (pinfunction "1_1") (pintype "passive"))
      (node (ref "DD4") (pin "18") (pinfunction "VSS_18") (pintype "passive"))
      (node (ref "DD4") (pin "60") (pinfunction "BOOT0_60") (pintype "passive"))
      (node (ref "DD4") (pin "63") (pinfunction "VSS_63") (pintype "passive"))
      (node (ref "DD5") (pin "1") (pinfunction "Vin-_1") (pintype "passive"))
      (node (ref "DD6") (pin "2") (pinfunction "GND1_2") (pintype "passive"))
      (node (ref "DD6") (pin "7") (pinfunction "GND1_7") (pintype "passive"))
      (node (ref "DD6") (pin "8") (pinfunction "GND1_8") (pintype "passive"))
      (node (ref "G1") (pin "2") (pinfunction "GND_2") (pintype "power_in"))
      (node (ref "X4") (pin "10") (pinfunction "10_10") (pintype "passive"))
      (node (ref "X4") (pin "9") (pinfunction "9_9") (pintype "passive"))
      (node (ref "X5") (pin "4") (pinfunction "4_4") (pintype "passive"))
      (node (ref "X6") (pin "5") (pinfunction "5_5") (pintype "passive"))
    )
    (net (code "38") (name "EGND") (class "Default")
      (node (ref "X5") (pin "5") (pinfunction "5_5") (pintype "passive"))
      (node (ref "X6") (pin "6") (pinfunction "6_6") (pintype "passive"))
      (node (ref "X7") (pin "1") (pinfunction "1_1") (pintype "passive"))
      (node (ref "X8") (pin "1") (pinfunction "1_1") (pintype "passive"))
    )
    (net (code "39") (name "GND_CAN") (class "Default")
      (node (ref "C70") (pin "2") (pinfunction "2_2") (pintype "passive"))
      (node (ref "C75") (pin "1") (pinfunction "1_1") (pintype "passive"))
      (node (ref "C78") (pin "1") (pinfunction "1_1") (pintype "passive"))
      (node (ref "C79") (pin "1") (pinfunction "1_1") (pintype "passive"))
      (node (ref "DA10") (pin "3") (pintype "passive"))
      (node (ref "DD5") (pin "3") (pinfunction "Vout-_3") (pintype "passive"))
      (node (ref "DD6") (pin "10") (pinfunction "GND2_10") (pintype "passive"))
      (node (ref "DD6") (pin "15") (pinfunction "GND2_15") (pintype "passive"))
      (node (ref "DD6") (pin "9") (pinfunction "GND2_9") (pintype "passive"))
      (node (ref "X8") (pin "2") (pinfunction "2_2") (pintype "passive"))
    )
    (net (code "40") (name "Net-(C67-Pad1)") (class "Default")
      (node (ref "C67") (pin "1") (pinfunction "1_1") (pintype "passive"))
      (node (ref "C68") (pin "2") (pinfunction "2_2") (pintype "passive"))
      (node (ref "R65") (pin "2") (pinfunction "2_2") (pintype "passive"))
      (node (ref "R66") (pin "1") (pinfunction "1_1") (pintype "passive"))
    )
    (net (code "41") (name "Net-(C68-Pad1)") (class "Default")
      (node (ref "C68") (pin "1") (pinfunction "1_1") (pintype "passive"))
      (node (ref "C73") (pin "2") (pinfunction "2_2") (pintype "passive"))
      (node (ref "R69") (pin "2") (pinfunction "2_2") (pintype "passive"))
      (node (ref "R70") (pin "1") (pinfunction "1_1") (pintype "passive"))
    )
    (net (code "42") (name "Net-(C75-Pad2)") (class "Default")
      (node (ref "C75") (pin "2") (pinfunction "2_2") (pintype "passive"))
      (node (ref "R73") (pin "1") (pinfunction "1_1") (pintype "passive"))
      (node (ref "R74") (pin "2") (pinfunction "2_2") (pintype "passive"))
    )
    (net (code "43") (name "Net-(DA9-+IN)") (class "Default")
      (node (ref "C71") (pin "2") (pinfunction "2_2") (pintype "passive"))
      (node (ref "DA9") (pin "1") (pinfunction "+IN_1") (pintype "passive"))
      (node (ref "R70") (pin "2") (pinfunction "2_2") (pintype "passive"))
      (node (ref "R71") (pin "2") (pinfunction "2_2") (pintype "passive"))
    )
    (net (code "44") (name "Net-(DA9--IN)") (class "Default")
      (node (ref "C66") (pin "2") (pinfunction "2_2") (pintype "passive"))
      (node (ref "DA9") (pin "3") (pinfunction "-IN_3") (pintype "passive"))
      (node (ref "R66") (pin "2") (pinfunction "2_2") (pintype "passive"))
      (node (ref "R67") (pin "1") (pinfunction "1_1") (pintype "passive"))
    )
    (net (code "45") (name "Net-(DA9-OUT)") (class "Default")
      (node (ref "C66") (pin "1") (pinfunction "1_1") (pintype "passive"))
      (node (ref "DA9") (pin "4") (pinfunction "OUT_4") (pintype "passive"))
      (node (ref "R67") (pin "2") (pinfunction "2_2") (pintype "passive"))
      (node (ref "R68") (pin "1") (pinfunction "1_1") (pintype "passive"))
    )
    (net (code "46") (name "Net-(DD4-PH0_{slash}OSC_IN{slash}FT)") (class "Default")
      (node (ref "DD4") (pin "5") (pinfunction "PH0_/OSC_IN/FT_5") (pintype "passive"))
      (node (ref "G1") (pin "3") (pinfunction "DCLK_3") (pintype "power_in"))
    )
    (net (code "47") (name "Net-(DD4-VCAP_1)") (class "Default")
      (node (ref "C54") (pin "2") (pinfunction "2_2") (pintype "passive"))
      (node (ref "DD4") (pin "31") (pinfunction "VCAP_1_31") (pintype "passive"))
    )
    (net (code "48") (name "Net-(DD4-VCAP_2)") (class "Default")
      (node (ref "C53") (pin "2") (pinfunction "2_2") (pintype "passive"))
      (node (ref "DD4") (pin "47") (pinfunction "VCAP_2_47") (pintype "passive"))
    )
    (net (code "49") (name "Net-(DD4-VDDA)") (class "Default")
      (node (ref "C56") (pin "2") (pinfunction "2_2") (pintype "passive"))
      (node (ref "C57") (pin "1") (pinfunction "1_1") (pintype "passive"))
      (node (ref "DD4") (pin "13") (pinfunction "VDDA_13") (pintype "passive"))
      (node (ref "L3") (pin "1") (pinfunction "1_1") (pintype "passive"))
    )
    (net (code "50") (name "Net-(R53-Pad1)") (class "Default")
      (node (ref "R53") (pin "1") (pinfunction "1_1") (pintype "passive"))
      (node (ref "X4") (pin "3") (pinfunction "3_3") (pintype "passive"))
    )
    (net (code "51") (name "Net-(R54-Pad1)") (class "Default")
      (node (ref "R54") (pin "1") (pinfunction "1_1") (pintype "passive"))
      (node (ref "X4") (pin "4") (pinfunction "4_4") (pintype "passive"))
    )
    (net (code "52") (name "Net-(R55-Pad1)") (class "Default")
      (node (ref "R55") (pin "1") (pinfunction "1_1") (pintype "passive"))
      (node (ref "X4") (pin "5") (pinfunction "5_5") (pintype "passive"))
    )
    (net (code "53") (name "Net-(R56-Pad1)") (class "Default")
      (node (ref "R56") (pin "1") (pinfunction "1_1") (pintype "passive"))
      (node (ref "X4") (pin "6") (pinfunction "6_6") (pintype "passive"))
    )
    (net (code "54") (name "Net-(R57-Pad1)") (class "Default")
      (node (ref "R57") (pin "1") (pinfunction "1_1") (pintype "passive"))
      (node (ref "X4") (pin "7") (pinfunction "7_7") (pintype "passive"))
    )
    (net (code "55") (name "Net-(R58-Pad1)") (class "Default")
      (node (ref "R58") (pin "1") (pinfunction "1_1") (pintype "passive"))
      (node (ref "X4") (pin "8") (pinfunction "8_8") (pintype "passive"))
    )
    (net (code "56") (name "Net-(VD5-K)") (class "Default")
      (node (ref "VD5") (pin "1") (pinfunction "K_1") (pintype "passive"))
      (node (ref "X4") (pin "1") (pinfunction "1_1") (pintype "passive"))
      (node (ref "X4") (pin "2") (pinfunction "2_2") (pintype "passive"))
    )
    (net (code "57") (name "unconnected-(DD4-A15_{slash}_JTDI{slash}SPI3_NSS{slash}I2S3_WS{slash}TIM2_CH1_ETR{slash}_SPI1_NSS{slash}FT-Pad50)") (class "Default")
      (node (ref "DD4") (pin "50") (pinfunction "A15_/_JTDI/SPI3_NSS/I2S3_WS/TIM2_CH1_ETR/_SPI1_NSS/FT_50") (pintype "passive"))
    )
    (net (code "58") (name "unconnected-(DD4-PA2_{slash}_USART2_TX{slash}TIM5_CH3{slash}ADC123_IN2{slash}TIM9_CH1{slash}TIM2_CH3{slash}ADC123_IN2{slash}FT-Pad16)") (class "Default")
      (node (ref "DD4") (pin "16") (pinfunction "PA2_/_USART2_TX/TIM5_CH3/ADC123_IN2/TIM9_CH1/TIM2_CH3/ADC123_IN2/FT_16") (pintype "passive"))
    )
    (net (code "59") (name "unconnected-(DD4-PA3_{slash}_USART2_RX{slash}TIM5_CH4{slash}TIM9_CH2{slash}TIM2_CH4{slash}OTG_HS_ULPI_D0{slash}ETH_MII_COL{slash}ADC123_IN3{slash}FT-Pad17)") (class "Default")
      (node (ref "DD4") (pin "17") (pinfunction "PA3_/_USART2_RX/TIM5_CH4/TIM9_CH2/TIM2_CH4/OTG_HS_ULPI_D0/ETH_MII_COL/ADC123_IN3/FT_17") (pintype "passive"))
    )
    (net (code "60") (name "unconnected-(DD4-PA4_{slash}_SPI1_NSS{slash}SPI3_NSS{slash}USART2_CK{slash}DCMI_HSYNC{slash}OTG_HS_SOF{slash}I2S3_WS{slash}ADC12_IN4{slash}DAC_OUT1{slash}TTa-Pad20)") (class "Default")
      (node (ref "DD4") (pin "20") (pinfunction "PA4_/_SPI1_NSS/SPI3_NSS/USART2_CK/DCMI_HSYNC/OTG_HS_SOF/I2S3_WS/ADC12_IN4/DAC_OUT1/TTa_20") (pintype "passive"))
    )
    (net (code "61") (name "unconnected-(DD4-PA5_{slash}_SPI1_SCK{slash}OTG_HS_ULPI_CK{slash}TIM2_CH1_ETR{slash}TIM8_CH1N{slash}ADC12_IN5{slash}DAC_OUT2{slash}TTa-Pad21)") (class "Default")
      (node (ref "DD4") (pin "21") (pinfunction "PA5_/_SPI1_SCK/OTG_HS_ULPI_CK/TIM2_CH1_ETR/TIM8_CH1N/ADC12_IN5/DAC_OUT2/TTa_21") (pintype "passive"))
    )
    (net (code "62") (name "unconnected-(DD4-PA6_{slash}_SPI1_MISO{slash}TIM8_BKIN{slash}TIM13_CH1{slash}DCMI_PIXCLK{slash}TIM3_CH1{slash}TIM1_BKIN{slash}ADC12_IN6{slash}FT-Pad22)") (class "Default")
      (node (ref "DD4") (pin "22") (pinfunction "PA6_/_SPI1_MISO/TIM8_BKIN/TIM13_CH1/DCMI_PIXCLK/TIM3_CH1/TIM1_BKIN/ADC12_IN6/FT_22") (pintype "passive"))
    )
    (net (code "63") (name "unconnected-(DD4-PA7_{slash}_SPI1_MOSI{slash}TIM8_CH1N{slash}TIM14_CH1{slash}TIM3_CH2{slash}ETH_MII_RX_DV{slash}TIM1_CH1N{slash}ETH_RMII_CRS_DV{slash}ADC12_IN7{slash}FT-Pad23)") (class "Default")
      (node (ref "DD4") (pin "23") (pinfunction "PA7_/_SPI1_MOSI/TIM8_CH1N/TIM14_CH1/TIM3_CH2/ETH_MII_RX_DV/TIM1_CH1N/ETH_RMII_CRS_DV/ADC12_IN7/FT_23") (pintype "passive"))
    )
    (net (code "64") (name "unconnected-(DD4-PB0_{slash}_TIM3_CH3{slash}TIM8_CH2N{slash}OTG_HS_ULPI_D1{slash}ETH_MII_RXD2{slash}TIM1_CH2N{slash}ADC12_IN8{slash}FT-Pad26)") (class "Default")
      (node (ref "DD4") (pin "26") (pinfunction "PB0_/_TIM3_CH3/TIM8_CH2N/OTG_HS_ULPI_D1/ETH_MII_RXD2/TIM1_CH2N/ADC12_IN8/FT_26") (pintype "passive"))
    )
    (net (code "65") (name "unconnected-(DD4-PB2_{slash}_BOOT1{slash}FT-Pad28)") (class "Default")
      (node (ref "DD4") (pin "28") (pinfunction "PB2_/_BOOT1/FT_28") (pintype "passive"))
    )
    (net (code "66") (name "unconnected-(DD4-PB4_{slash}_NJTRST{slash}SPI3_MISO{slash}TIM3_CH1{slash}SPI1_MISO{slash}I2S3ext_SD{slash}FT-Pad56)") (class "Default")
      (node (ref "DD4") (pin "56") (pinfunction "PB4_/_NJTRST/SPI3_MISO/TIM3_CH1/SPI1_MISO/I2S3ext_SD/FT_56") (pintype "passive"))
    )
    (net (code "67") (name "unconnected-(DD4-PB5_{slash}_I2C1_SMBA{slash}CAN2_RX{slash}OTG_HS_ULPI_D7{slash}ETH_PPS_OUT{slash}TIM3_CH2{slash}SPI1_MOSI{slash}SPI3_MOSI{slash}DCMI_D10{slash}I2S3_SD{slash}FT-Pad57)") (class "Default")
      (node (ref "DD4") (pin "57") (pinfunction "PB5_/_I2C1_SMBA/CAN2_RX/OTG_HS_ULPI_D7/ETH_PPS_OUT/TIM3_CH2/SPI1_MOSI/SPI3_MOSI/DCMI_D10/I2S3_SD/FT_57") (pintype "passive"))
    )
    (net (code "68") (name "unconnected-(DD4-PB8_{slash}_TIM4_CH3{slash}SDIO_D4{slash}TIM10_CH1{slash}DCMI_D6{slash}ETH_MII_TXD3{slash}I2C1_SCL{slash}CAN1_RX{slash}FT-Pad61)") (class "Default")
      (node (ref "DD4") (pin "61") (pinfunction "PB8_/_TIM4_CH3/SDIO_D4/TIM10_CH1/DCMI_D6/ETH_MII_TXD3/I2C1_SCL/CAN1_RX/FT_61") (pintype "passive"))
    )
    (net (code "69") (name "unconnected-(DD4-PB9_{slash}_SPI2_NSS{slash}I2S2_WS{slash}TIM4_CH4{slash}TIM11_CH1{slash}SDIO_D5{slash}DCMI_D7{slash}I2C1_SDA{slash}CAN1_TX{slash}FT-Pad62)") (class "Default")
      (node (ref "DD4") (pin "62") (pinfunction "PB9_/_SPI2_NSS/I2S2_WS/TIM4_CH4/TIM11_CH1/SDIO_D5/DCMI_D7/I2C1_SDA/CAN1_TX/FT_62") (pintype "passive"))
    )
    (net (code "70") (name "unconnected-(DD4-PC2_{slash}_SPI2_MISO{slash}OTG_HS_ULPI_DIR{slash}ETH_MII_TXD2{slash}I2S2ext_SD{slash}ADC123_IN12{slash}FT-Pad10)") (class "Default")
      (node (ref "DD4") (pin "10") (pinfunction "PC2_/_SPI2_MISO/OTG_HS_ULPI_DIR/ETH_MII_TXD2/I2S2ext_SD/ADC123_IN12/FT_10") (pintype "passive"))
    )
    (net (code "71") (name "unconnected-(DD4-PC3_{slash}_SPI2_MOSI{slash}I2S2_SD{slash}OTG_HS_ULPI_NXT{slash}ETH_MII_TX_CLK{slash}ADC123_IN13{slash}FT-Pad11)") (class "Default")
      (node (ref "DD4") (pin "11") (pinfunction "PC3_/_SPI2_MOSI/I2S2_SD/OTG_HS_ULPI_NXT/ETH_MII_TX_CLK/ADC123_IN13/FT_11") (pintype "passive"))
    )
    (net (code "72") (name "unconnected-(DD4-PC4_{slash}_ETH_RMII_RX_D0{slash}ETH_MII_RX_D0{slash}ADC12_IN14{slash}FT-Pad24)") (class "Default")
      (node (ref "DD4") (pin "24") (pinfunction "PC4_/_ETH_RMII_RX_D0/ETH_MII_RX_D0/ADC12_IN14/FT_24") (pintype "passive"))
    )
    (net (code "73") (name "unconnected-(DD4-PC5_{slash}_ETH_RMII_RX_D1{slash}ETH_MII_RX_D1{slash}ADC12_IN15{slash}FT-Pad25)") (class "Default")
      (node (ref "DD4") (pin "25") (pinfunction "PC5_/_ETH_RMII_RX_D1/ETH_MII_RX_D1/ADC12_IN15/FT_25") (pintype "passive"))
    )
    (net (code "74") (name "unconnected-(DD4-PC6_{slash}_I2S2_MCK{slash}TIM8_CH1{slash}SDIO_D6{slash}USART6_TX{slash}DCMI_D0{slash}TIM3_CH1{slash}FT-Pad37)") (class "Default")
      (node (ref "DD4") (pin "37") (pinfunction "PC6_/_I2S2_MCK/TIM8_CH1/SDIO_D6/USART6_TX/DCMI_D0/TIM3_CH1/FT_37") (pintype "passive"))
    )
    (net (code "75") (name "unconnected-(DD4-PC9_{slash}_I2S_CKIN{slash}MCO2{slash}TIM8_CH4{slash}SDIO_D1{slash}I2C3_SDA{slash}DCMI_D3{slash}TIM3_CH4{slash}FT-Pad40)") (class "Default")
      (node (ref "DD4") (pin "40") (pinfunction "PC9_/_I2S_CKIN/MCO2/TIM8_CH4/SDIO_D1/I2C3_SDA/DCMI_D3/TIM3_CH4/FT_40") (pintype "passive"))
    )
    (net (code "76") (name "unconnected-(DD4-PC10_{slash}_SPI3_SCK{slash}I2S3_CK{slash}UART4_TX{slash}SDIO_D2{slash}DCMI_D8{slash}USART3_TX{slash}FT-Pad51)") (class "Default")
      (node (ref "DD4") (pin "51") (pinfunction "PC10_/_SPI3_SCK/I2S3_CK/UART4_TX/SDIO_D2/DCMI_D8/USART3_TX/FT_51") (pintype "passive"))
    )
    (net (code "77") (name "unconnected-(DD4-PC11_{slash}_UART4_RX{slash}SPI3_MISO{slash}SDIO_D3{slash}DCMI_D4{slash}USART3_RX{slash}I2S3ext_SD{slash}FT-Pad52)") (class "Default")
      (node (ref "DD4") (pin "52") (pinfunction "PC11_/_UART4_RX/SPI3_MISO/SDIO_D3/DCMI_D4/USART3_RX/I2S3ext_SD/FT_52") (pintype "passive"))
    )
    (net (code "78") (name "unconnected-(DD4-PC12_{slash}_UART5_TX{slash}SDIO_CK{slash}DCMI_D9{slash}SPI3_MOSI{slash}I2S3_SD{slash}USART3_CK{slash}FT-Pad53)") (class "Default")
      (node (ref "DD4") (pin "53") (pinfunction "PC12_/_UART5_TX/SDIO_CK/DCMI_D9/SPI3_MOSI/I2S3_SD/USART3_CK/FT_53") (pintype "passive"))
    )
    (net (code "79") (name "unconnected-(DD4-PC13_{slash}_EVENTOUT{slash}RTC_OUT{slash}RTC_TAMP1{slash}RTC_TS{slash}FT-Pad2)") (class "Default")
      (node (ref "DD4") (pin "2") (pinfunction "PC13_/_EVENTOUT/RTC_OUT/RTC_TAMP1/RTC_TS/FT_2") (pintype "passive"))
    )
    (net (code "80") (name "unconnected-(DD4-PC14_{slash}_OSC32_IN{slash}FT-Pad3)") (class "Default")
      (node (ref "DD4") (pin "3") (pinfunction "PC14_/_OSC32_IN/FT_3") (pintype "passive"))
    )
    (net (code "81") (name "unconnected-(DD4-PC15_{slash}_OSC32_OUT{slash}FT-Pad4)") (class "Default")
      (node (ref "DD4") (pin "4") (pinfunction "PC15_/_OSC32_OUT/FT_4") (pintype "passive"))
    )
    (net (code "82") (name "unconnected-(DD4-PD2_{slash}_TIM3_ETR{slash}UART5_RX{slash}SDIO_CMD{slash}DCMI_D11{slash}FT-Pad54)") (class "Default")
      (node (ref "DD4") (pin "54") (pinfunction "PD2_/_TIM3_ETR/UART5_RX/SDIO_CMD/DCMI_D11/FT_54") (pintype "passive"))
    )
    (net (code "83") (name "unconnected-(DD4-PH1_{slash}OSC_OUT{slash}FT-Pad6)") (class "Default")
      (node (ref "DD4") (pin "6") (pinfunction "PH1_/OSC_OUT/FT_6") (pintype "passive+no_connect"))
    )
    (net (code "84") (name "unconnected-(DD6-NC-Pad4)") (class "Default")
      (node (ref "DD6") (pin "4") (pinfunction "NC_4") (pintype "passive+no_connect"))
    )
    (net (code "85") (name "unconnected-(DD6-NC-Pad5)") (class "Default")
      (node (ref "DD6") (pin "5") (pinfunction "NC_5") (pintype "passive+no_connect"))
    )
    (net (code "86") (name "unconnected-(DD6-NC-Pad11)") (class "Default")
      (node (ref "DD6") (pin "11") (pinfunction "NC_11") (pintype "passive+no_connect"))
    )
    (net (code "87") (name "unconnected-(DD6-NC-Pad14)") (class "Default")
      (node (ref "DD6") (pin "14") (pinfunction "NC_14") (pintype "passive+no_connect"))
    )
    (net (code "88") (name "unconnected-(G1-NC-Pad1)") (class "Default")
      (node (ref "G1") (pin "1") (pinfunction "NC_1") (pintype "power_in+no_connect"))
    )
  )
)
